# Peripherals.net
KiCad netlist of a schematic drawn in Altium Designer
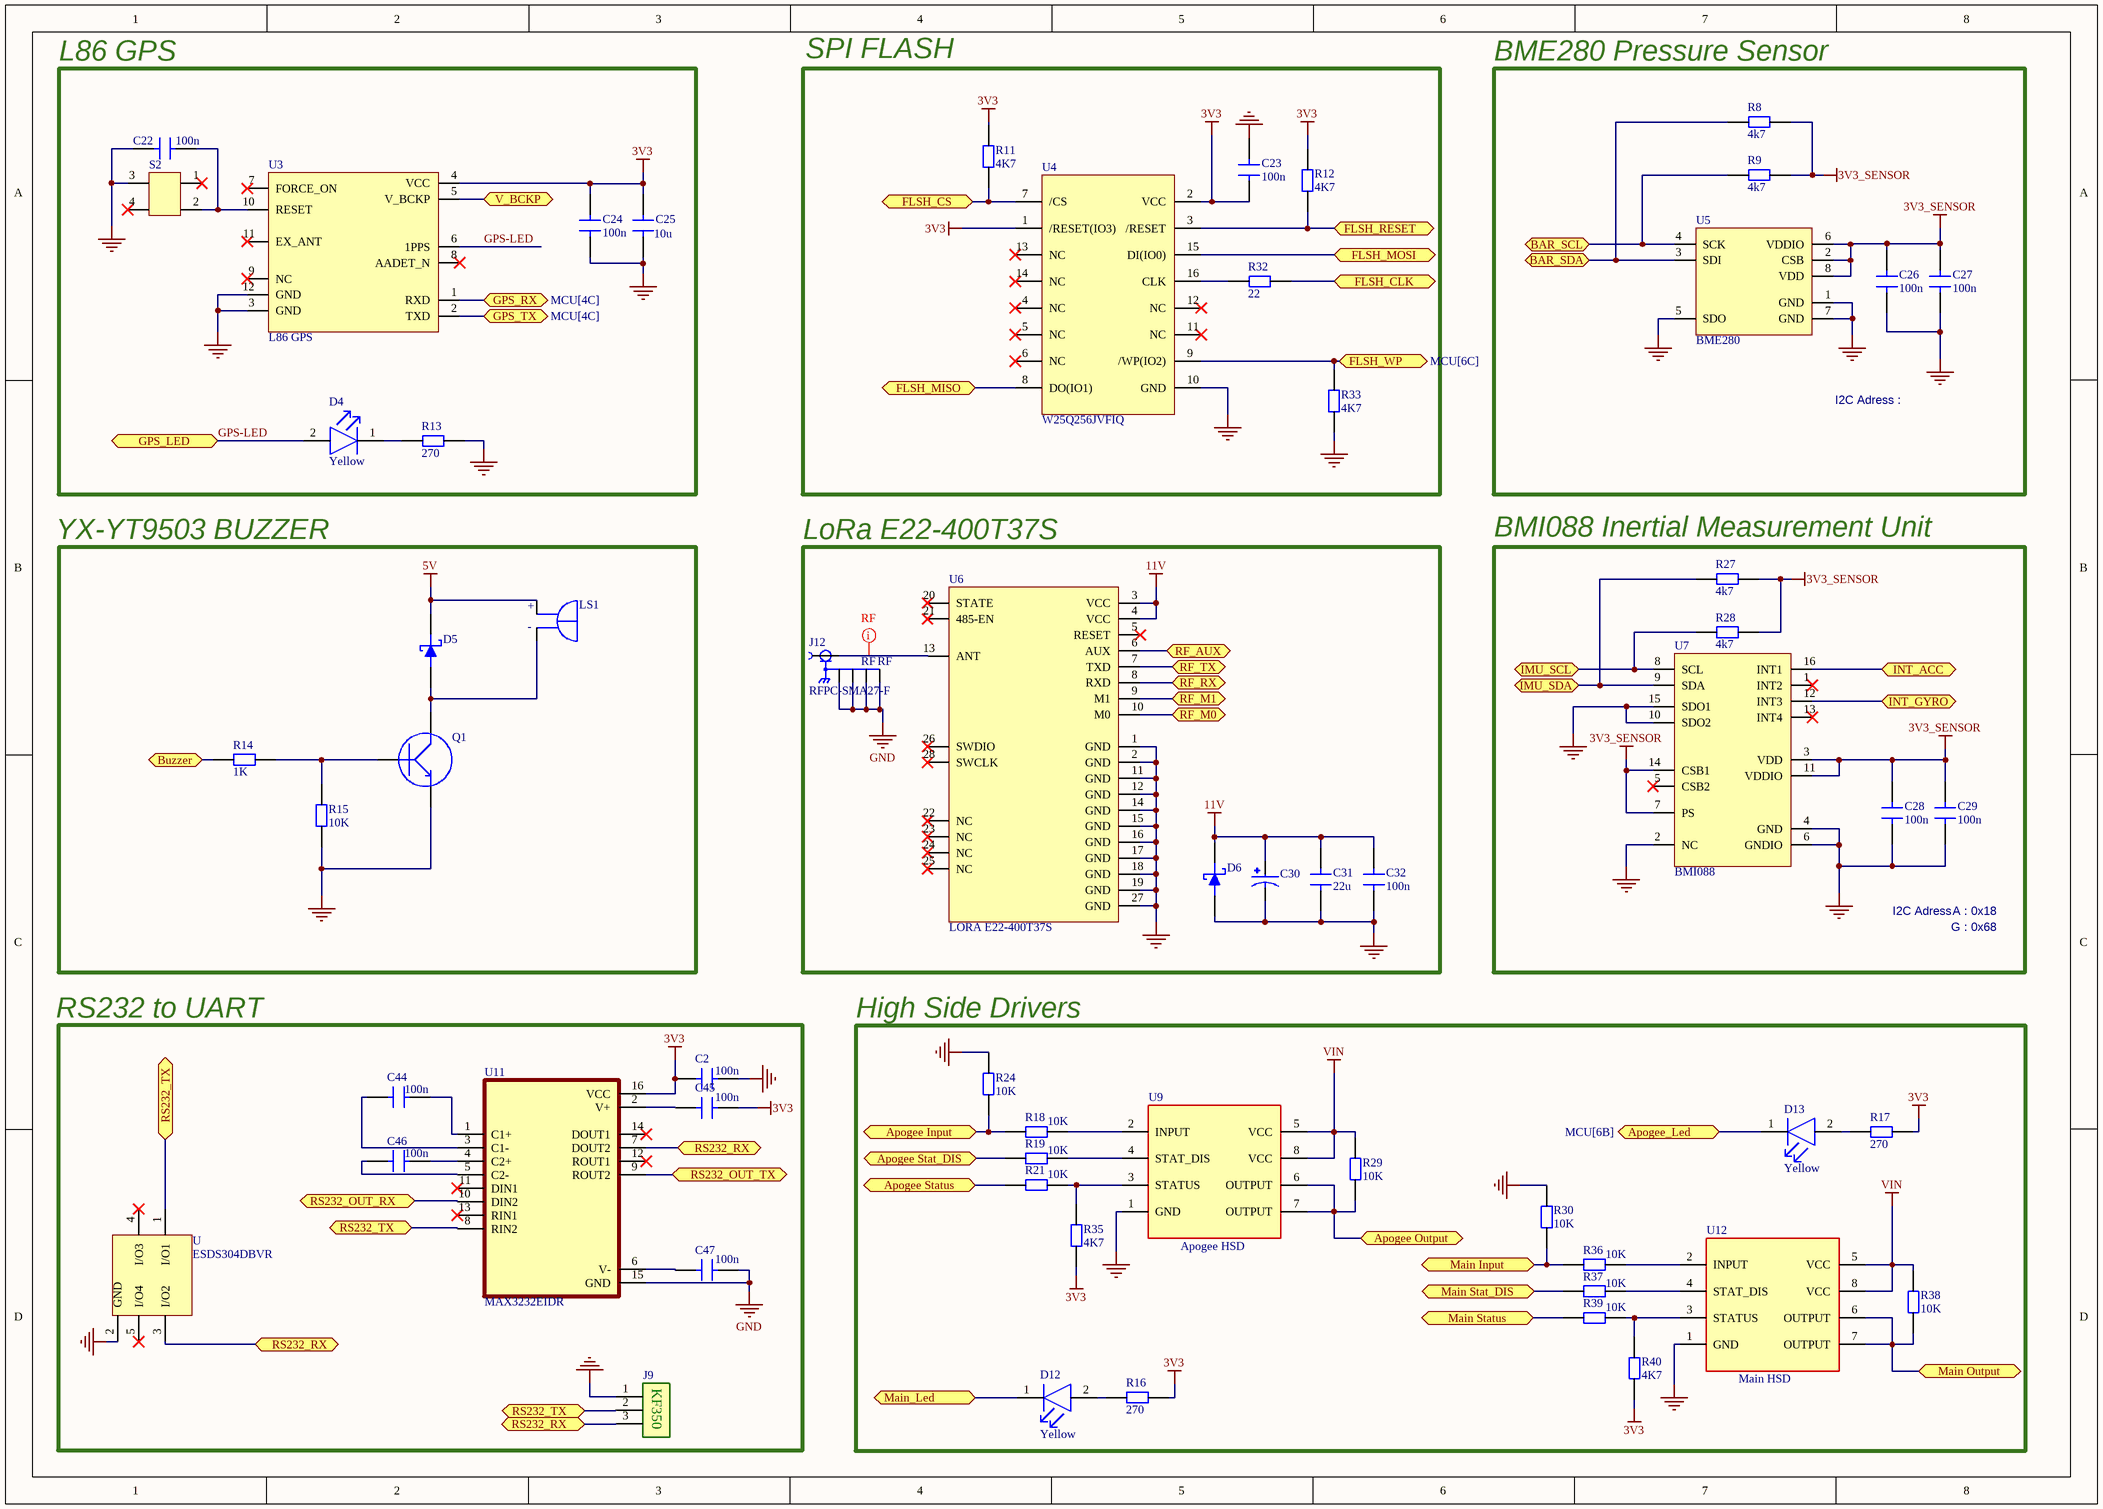
[diagram p0: Peripherals.SchDoc]

(export (version "E")
  (design (tool "Eeschema 10.0.6"))
  (components
    (comp (ref "C2")
      (value "100n")
      (footprint "CAP 0603")
      (description "Capacitor SMD 0603 25V")
      (libsource (lib "R_07_24-Schlib") (part "CAP 0603 25V"))
    )
    (comp (ref "C22")
      (value "100n")
      (footprint "CAP 0603")
      (description "Capacitor SMD 0603 50V")
      (libsource (lib "Schlib") (part "CAP 0603 50V"))
    )
    (comp (ref "C23")
      (value "100n")
      (footprint "CAP 0603")
      (description "Capacitor SMD 0603 50V")
      (libsource (lib "R_07_24-Schlib") (part "CAP 0603 50V"))
    )
    (comp (ref "C24")
      (value "100n")
      (footprint "CAP 0805")
      (description "Capacitor SMD 0805 50V")
      (libsource (lib "R_07_24-Schlib") (part "CAP 0805 50V"))
    )
    (comp (ref "C25")
      (value "10u")
      (footprint "CAP 0805")
      (description "Capacitor SMD 0805 25V")
      (libsource (lib "Schlib") (part "CAP 0805 25V"))
    )
    (comp (ref "C26")
      (value "100n")
      (footprint "CAP 0603")
      (description "Capacitor SMD 0603 50V")
      (libsource (lib "Schlib") (part "CAP 0603 50V"))
    )
    (comp (ref "C27")
      (value "100n")
      (footprint "CAP 0603")
      (description "Capacitor SMD 0603 50V")
      (libsource (lib "Schlib") (part "CAP 0603 50V"))
    )
    (comp (ref "C28")
      (value "100n")
      (footprint "CAP 0603")
      (description "Capacitor SMD 0603 50V")
      (libsource (lib "Schlib") (part "CAP 0603 50V"))
    )
    (comp (ref "C29")
      (value "100n")
      (footprint "CAP 0603")
      (description "Capacitor SMD 0603 50V")
      (libsource (lib "Schlib") (part "CAP 0603 50V"))
    )
    (comp (ref "C30")
      (value "EEEFK1E101XP")
      (footprint "CAP_EEEFK1E101XP")
      (fields (field (name "MF") "Panasonic"))
      (libsource (lib "2024_Temmuz") (part "100uF AL CAP"))
    )
    (comp (ref "C31")
      (value "22u")
      (footprint "CAP 1210")
      (description "Capacitor SMD 1210 25V")
      (libsource (lib "Schlib") (part "CAP 1210 25V"))
    )
    (comp (ref "C32")
      (value "100n")
      (footprint "CAP 0805")
      (description "Capacitor SMD 0805 50V")
      (libsource (lib "Schlib") (part "CAP 0805 50V"))
    )
    (comp (ref "C44")
      (value "100n")
      (footprint "CAP 0603")
      (description "Capacitor SMD 0603 25V")
      (libsource (lib "R_07_24-Schlib") (part "CAP 0603 25V"))
    )
    (comp (ref "C45")
      (value "100n")
      (footprint "CAP 0603")
      (description "Capacitor SMD 0603 25V")
      (libsource (lib "R_07_24-Schlib") (part "CAP 0603 25V"))
    )
    (comp (ref "C46")
      (value "100n")
      (footprint "CAP 0603")
      (description "Capacitor SMD 0603 25V")
      (libsource (lib "R_07_24-Schlib") (part "CAP 0603 25V"))
    )
    (comp (ref "C47")
      (value "100n")
      (footprint "CAP 0603")
      (description "Capacitor SMD 0603 25V")
      (libsource (lib "R_07_24-Schlib") (part "CAP 0603 25V"))
    )
    (comp (ref "D4")
      (value "Yellow")
      (footprint "FP-LTST-C170YKT-MFG")
      (description "LED YELLOW CLEAR SMD")
      (libsource (lib "Altium Content Vault") (part "590121a5bdfd2d28d8ee457b77c7368"))
    )
    (comp (ref "D5")
      (value "TMBAT49FILM")
      (footprint "TMBAT49FILM")
      (description "Rectifier Diode Small Signal Schottky Si 80V 0.5A 2-Pin MELF T/R")
      (fields (field (name "MANUFACTURER") "STMicroelectronics"))
      (libsource (lib "Schlib") (part "TMBAT49FILM"))
    )
    (comp (ref "D6")
      (value "SMBJ14CA")
      (footprint "SMBJ12CA-13-F")
      (description "TVS DIODE 14VWM 23.2VC DO214AA")
      (fields (field (name "MANUFACTURER") "Littelfuse") (field (name "VOLTAGE") "14V"))
      (libsource (lib "Schlib") (part "SMBJ14CA"))
    )
    (comp (ref "D12")
      (value "Yellow")
      (footprint "FP-LTST-C170YKT-MFG")
      (description "LED YELLOW CLEAR SMD")
      (libsource (lib "Altium Content Vault") (part "590121a5bdfd2d28d8ee457b77c7368"))
    )
    (comp (ref "D13")
      (value "Yellow")
      (footprint "FP-LTST-C170YKT-MFG")
      (description "LED YELLOW CLEAR SMD")
      (libsource (lib "Altium Content Vault") (part "590121a5bdfd2d28d8ee457b77c7368"))
    )
    (comp (ref "J9")
      (value "KF350-3P")
      (footprint "KF350-3P")
      (libsource (lib "2024_Temmuz") (part "KF350-3P"))
    )
    (comp (ref "J12")
      (value "RFPC-SMA27-F")
      (footprint "GRADCONN_RFPC-SMA27-F")
      (fields (field (name "MF") "{'manufacturer': u'GradConn'}"))
      (libsource (lib "2024_Temmuz") (part "RFPC-SMA27-F"))
    )
    (comp (ref "LS1")
      (value "KXG0912C")
      (footprint "XDCR_KXG0912C")
      (libsource (lib "2024_Temmuz") (part "KXG0912C"))
    )
    (comp (ref "Q1")
      (value "BC817-25W,115")
      (footprint "BC817-25")
      (description "BC817 Series 45 V 500 mA NPN General Purpose Transistor - SOT-23")
      (fields (field (name "MANUFACTURER") "Nexperia"))
      (libsource (lib "Schlib") (part "BC817-25W,115"))
    )
    (comp (ref "R8")
      (value "4k7")
      (footprint "RES 0603")
      (description "Resistor SMD 0603")
      (libsource (lib "Schlib") (part "RES 0603"))
    )
    (comp (ref "R9")
      (value "4k7")
      (footprint "RES 0603")
      (description "Resistor SMD 0603")
      (libsource (lib "Schlib") (part "RES 0603"))
    )
    (comp (ref "R11")
      (value "4K7")
      (footprint "RES 0805")
      (description "Resistor SMD 0805")
      (libsource (lib "R_07_24-Schlib") (part "RES 0805"))
    )
    (comp (ref "R12")
      (value "4K7")
      (footprint "RES 0805")
      (description "Resistor SMD 0805")
      (libsource (lib "R_07_24-Schlib") (part "RES 0805"))
    )
    (comp (ref "R13")
      (value "270")
      (footprint "RES 0805")
      (description "Resistor SMD 0805")
      (libsource (lib "R_07_24-Schlib") (part "RES 0805"))
    )
    (comp (ref "R14")
      (value "1K")
      (footprint "RES 0805")
      (description "Resistor SMD 0805")
      (libsource (lib "R_07_24-Schlib") (part "RES 0805"))
    )
    (comp (ref "R15")
      (value "10K")
      (footprint "RES 0805")
      (description "Resistor SMD 0805")
      (libsource (lib "R_07_24-Schlib") (part "RES 0805"))
    )
    (comp (ref "R16")
      (value "270")
      (footprint "RES 0805")
      (description "Resistor SMD 0805")
      (libsource (lib "R_07_24-Schlib") (part "RES 0805"))
    )
    (comp (ref "R17")
      (value "270")
      (footprint "RES 0805")
      (description "Resistor SMD 0805")
      (libsource (lib "R_07_24-Schlib") (part "RES 0805"))
    )
    (comp (ref "R18")
      (value "10K")
      (footprint "RES 0603")
      (description "Resistor SMD 0603")
      (libsource (lib "R_07_24-Schlib") (part "RES 0603"))
    )
    (comp (ref "R19")
      (value "10K")
      (footprint "RES 0603")
      (description "Resistor SMD 0603")
      (libsource (lib "R_07_24-Schlib") (part "RES 0603"))
    )
    (comp (ref "R21")
      (value "10K")
      (footprint "RES 0603")
      (description "Resistor SMD 0603")
      (libsource (lib "R_07_24-Schlib") (part "RES 0603"))
    )
    (comp (ref "R24")
      (value "10K")
      (footprint "RES 0603")
      (description "Resistor SMD 0603")
      (libsource (lib "R_07_24-Schlib") (part "RES 0603"))
    )
    (comp (ref "R27")
      (value "4k7")
      (footprint "RES 0603")
      (description "Resistor SMD 0603")
      (libsource (lib "Schlib") (part "RES 0603"))
    )
    (comp (ref "R28")
      (value "4k7")
      (footprint "RES 0603")
      (description "Resistor SMD 0603")
      (libsource (lib "Schlib") (part "RES 0603"))
    )
    (comp (ref "R29")
      (value "10K")
      (footprint "RES 0805")
      (description "Resistor SMD 0805")
      (libsource (lib "R_07_24-Schlib") (part "RES 0805"))
    )
    (comp (ref "R30")
      (value "10K")
      (footprint "RES 0603")
      (description "Resistor SMD 0603")
      (libsource (lib "R_07_24-Schlib") (part "RES 0603"))
    )
    (comp (ref "R32")
      (value "22")
      (footprint "RES 0603")
      (description "Resistor SMD 0603")
      (libsource (lib "R_07_24-Schlib") (part "RES 0603"))
    )
    (comp (ref "R33")
      (value "4K7")
      (footprint "RES 0603")
      (description "Resistor SMD 0603")
      (libsource (lib "") (part "RES 0603_1"))
    )
    (comp (ref "R35")
      (value "4K7")
      (footprint "RES 0603")
      (description "Resistor SMD 0603")
      (libsource (lib "R_07_24-Schlib") (part "RES 0603"))
    )
    (comp (ref "R36")
      (value "10K")
      (footprint "RES 0603")
      (description "Resistor SMD 0603")
      (libsource (lib "R_07_24-Schlib") (part "RES 0603"))
    )
    (comp (ref "R37")
      (value "10K")
      (footprint "RES 0603")
      (description "Resistor SMD 0603")
      (libsource (lib "R_07_24-Schlib") (part "RES 0603"))
    )
    (comp (ref "R38")
      (value "10K")
      (footprint "RES 0805")
      (description "Resistor SMD 0805")
      (libsource (lib "R_07_24-Schlib") (part "RES 0805"))
    )
    (comp (ref "R39")
      (value "10K")
      (footprint "RES 0603")
      (description "Resistor SMD 0603")
      (libsource (lib "R_07_24-Schlib") (part "RES 0603"))
    )
    (comp (ref "R40")
      (value "4K7")
      (footprint "RES 0603")
      (description "Resistor SMD 0603")
      (libsource (lib "R_07_24-Schlib") (part "RES 0603"))
    )
    (comp (ref "S2")
      (value "FSM4JSMATR")
      (footprint "FSM4JSMATR")
      (description "Switch Tactile OFF (ON) SPST Round Button Gull Wing 0.05A 24VDC 1.57N SMD T/R")
      (fields (field (name "MANUFACTURER") "TE Connectivity Alcoswitch"))
      (libsource (lib "Schlib") (part "FSM4JSMATR"))
    )
    (comp (ref "U")
      (value "ESDS304DBVR")
      (footprint "SOT95P280X145-5N")
      (description "2-channel, 3.6-V data-line surge and 30k-V ESD protection diode array 5-SOT-23 -40 to 125")
      (fields (field (name "MF") "Texas Instruments"))
      (libsource (lib "2024_Temmuz") (part "ESDS304DBVR"))
    )
    (comp (ref "U3") (value "L86 GPS") (footprint "L86") (libsource (lib "Schlib") (part "L86 GPS")))
    (comp (ref "U4")
      (value "W25Q256JVFIQ")
      (footprint "W25Q256JVFIQ")
      (libsource (lib "R_07_24-Schlib") (part "W25Q256JVFIQ"))
    )
    (comp (ref "U5")
      (value "BME280")
      (footprint "BME280")
      (description "SENSOR PRESSURE HUMIDITY TEMP")
      (fields (field (name "MANUFACTURER") "Bosch"))
      (libsource (lib "Schlib") (part "BME280"))
    )
    (comp (ref "U6")
      (value "LORA E22-400T37S")
      (footprint "LORA E22-400T37S")
      (description "E22-400T37S LoRa Module")
      (libsource (lib "Schlib") (part "LORA E22-400T37S"))
    )
    (comp (ref "U7")
      (value "BMI088")
      (footprint "BMI088")
      (description "BMI088 Series 3.6 V 6 Axis Digital Output Accelerometer Motion Sensor - LGA-16")
      (fields (field (name "MANUFACTURER") "Bosch Tools"))
      (libsource (lib "Schlib") (part "BMI088"))
    )
    (comp (ref "U9")
      (value "VN5E160STR-E")
      (footprint "VN5E160STR-E")
      (description "Power Switch/Driver 1:1 N-Channel 7A 8-SOIC \r\nHigh Side Driver")
      (fields (field (name "MF") "STMicroelectronics"))
      (libsource (lib "2024_Temmuz") (part "VN5E160STR-E"))
    )
    (comp (ref "U11")
      (value "MAX3232EIDR")
      (footprint "MAX3232EIDR")
      (description "3- to 5.5-V dual channel 250kbps RS-232 line driver/receiver with +/-15-kV IEC-ESD protection")
      (fields (field (name "MF") "Texas Instruments"))
      (libsource (lib "2024_Temmuz") (part "MAX3232EIDR"))
    )
    (comp (ref "U12")
      (value "VN5E160STR-E")
      (footprint "VN5E160STR-E")
      (description "Power Switch/Driver 1:1 N-Channel 7A 8-SOIC \r\nHigh Side Driver")
      (fields (field (name "MF") "STMicroelectronics"))
      (libsource (lib "2024_Temmuz") (part "VN5E160STR-E"))
    )
  )
  (nets
    (net (code "1") (name "/Apogee Input") (class "Default")
      (node (ref "R18") (pin "1") (pinfunction "1_1") (pintype "passive"))
      (node (ref "R24") (pin "1") (pinfunction "1_1") (pintype "passive"))
    )
    (net (code "2") (name "/Apogee Output") (class "Default")
      (node (ref "R29") (pin "1") (pinfunction "1_1") (pintype "passive"))
      (node (ref "U9") (pin "6") (pinfunction "OUTPUT_6") (pintype "passive"))
      (node (ref "U9") (pin "7") (pinfunction "OUTPUT_7") (pintype "passive"))
    )
    (net (code "3") (name "/Apogee Stat_DIS") (class "Default")
      (node (ref "R19") (pin "1") (pinfunction "1_1") (pintype "passive"))
    )
    (net (code "4") (name "/Apogee Status") (class "Default")
      (node (ref "R21") (pin "1") (pinfunction "1_1") (pintype "passive"))
    )
    (net (code "5") (name "/Apogee_Led") (class "Default")
      (node (ref "D13") (pin "1") (pinfunction "C_1") (pintype "passive"))
    )
    (net (code "6") (name "/BAR_SCL") (class "Default")
      (node (ref "R9") (pin "1") (pinfunction "1_1") (pintype "passive"))
      (node (ref "U5") (pin "4") (pinfunction "SCK_4") (pintype "passive"))
    )
    (net (code "7") (name "/BAR_SDA") (class "Default")
      (node (ref "R8") (pin "1") (pinfunction "1_1") (pintype "passive"))
      (node (ref "U5") (pin "3") (pinfunction "SDI_3") (pintype "passive"))
    )
    (net (code "8") (name "/Buzzer") (class "Default")
      (node (ref "R14") (pin "1") (pinfunction "1_1") (pintype "passive"))
    )
    (net (code "9") (name "/FLSH_CLK") (class "Default")
      (node (ref "R32") (pin "2") (pinfunction "2_2") (pintype "passive"))
    )
    (net (code "10") (name "/FLSH_CS") (class "Default")
      (node (ref "R11") (pin "1") (pinfunction "1_1") (pintype "passive"))
      (node (ref "U4") (pin "7") (pinfunction "/CS_7") (pintype "passive"))
    )
    (net (code "11") (name "/FLSH_MISO") (class "Default")
      (node (ref "U4") (pin "8") (pinfunction "DO(IO1)_8") (pintype "passive"))
    )
    (net (code "12") (name "/FLSH_MOSI") (class "Default")
      (node (ref "U4") (pin "15") (pinfunction "DI(IO0)_15") (pintype "passive"))
    )
    (net (code "13") (name "/FLSH_RESET") (class "Default")
      (node (ref "R12") (pin "1") (pinfunction "1_1") (pintype "passive"))
      (node (ref "U4") (pin "3") (pinfunction "/RESET_3") (pintype "passive"))
    )
    (net (code "14") (name "/FLSH_WP") (class "Default")
      (node (ref "R33") (pin "2") (pinfunction "2_2") (pintype "passive"))
      (node (ref "U4") (pin "9") (pinfunction "/WP(IO2)_9") (pintype "passive"))
    )
    (net (code "15") (name "/GPS-LED") (class "Default")
      (node (ref "D4") (pin "2") (pinfunction "A_2") (pintype "passive"))
      (node (ref "U3") (pin "6") (pinfunction "1PPS_6") (pintype "passive"))
    )
    (net (code "16") (name "/GPS_RX") (class "Default")
      (node (ref "U3") (pin "1") (pinfunction "RXD_1") (pintype "passive"))
    )
    (net (code "17") (name "/GPS_TX") (class "Default")
      (node (ref "U3") (pin "2") (pinfunction "TXD_2") (pintype "passive"))
    )
    (net (code "18") (name "/IMU_SCL") (class "Default")
      (node (ref "R28") (pin "1") (pinfunction "1_1") (pintype "passive"))
      (node (ref "U7") (pin "8") (pinfunction "SCL_8") (pintype "passive"))
    )
    (net (code "19") (name "/IMU_SDA") (class "Default")
      (node (ref "R27") (pin "1") (pinfunction "1_1") (pintype "passive"))
      (node (ref "U7") (pin "9") (pinfunction "SDA_9") (pintype "passive"))
    )
    (net (code "20") (name "/INT_ACC") (class "Default")
      (node (ref "U7") (pin "16") (pinfunction "INT1_16") (pintype "passive"))
    )
    (net (code "21") (name "/INT_GYRO") (class "Default")
      (node (ref "U7") (pin "12") (pinfunction "INT3_12") (pintype "passive"))
    )
    (net (code "23") (name "/Main Input") (class "Default")
      (node (ref "R30") (pin "1") (pinfunction "1_1") (pintype "passive"))
      (node (ref "R36") (pin "1") (pinfunction "1_1") (pintype "passive"))
    )
    (net (code "24") (name "/Main Output") (class "Default")
      (node (ref "R38") (pin "1") (pinfunction "1_1") (pintype "passive"))
      (node (ref "U12") (pin "6") (pinfunction "OUTPUT_6") (pintype "passive"))
      (node (ref "U12") (pin "7") (pinfunction "OUTPUT_7") (pintype "passive"))
    )
    (net (code "25") (name "/Main Stat_DIS") (class "Default")
      (node (ref "R37") (pin "1") (pinfunction "1_1") (pintype "passive"))
    )
    (net (code "26") (name "/Main Status") (class "Default")
      (node (ref "R39") (pin "1") (pinfunction "1_1") (pintype "passive"))
    )
    (net (code "27") (name "/Main_Led") (class "Default")
      (node (ref "D12") (pin "1") (pinfunction "C_1") (pintype "passive"))
    )
    (net (code "28") (name "/RF_AUX") (class "Default")
      (node (ref "U6") (pin "6") (pinfunction "AUX_6") (pintype "passive"))
    )
    (net (code "29") (name "/RF_M0") (class "Default")
      (node (ref "U6") (pin "10") (pinfunction "M0_10") (pintype "passive"))
    )
    (net (code "30") (name "/RF_M1") (class "Default")
      (node (ref "U6") (pin "9") (pinfunction "M1_9") (pintype "passive"))
    )
    (net (code "31") (name "/RF_RX") (class "Default")
      (node (ref "U6") (pin "8") (pinfunction "RXD_8") (pintype "passive"))
    )
    (net (code "32") (name "/RF_TX") (class "Default")
      (node (ref "U6") (pin "7") (pinfunction "TXD_7") (pintype "passive"))
    )
    (net (code "33") (name "/RS232_OUT_RX") (class "Default")
      (node (ref "U11") (pin "10") (pinfunction "DIN2_10") (pintype "passive"))
    )
    (net (code "34") (name "/RS232_OUT_TX") (class "Default")
      (node (ref "U11") (pin "9") (pinfunction "ROUT2_9") (pintype "passive"))
    )
    (net (code "35") (name "/RS232_RX") (class "Default")
      (node (ref "J9") (pin "3") (pinfunction "3_3") (pintype "passive"))
      (node (ref "U") (pin "3") (pinfunction "I/O2_3") (pintype "passive"))
      (node (ref "U11") (pin "7") (pinfunction "DOUT2_7") (pintype "passive"))
    )
    (net (code "36") (name "/RS232_TX") (class "Default")
      (node (ref "J9") (pin "2") (pinfunction "2_2") (pintype "passive"))
      (node (ref "U") (pin "1") (pinfunction "I/O1_1") (pintype "passive"))
      (node (ref "U11") (pin "8") (pinfunction "RIN2_8") (pintype "passive"))
    )
    (net (code "37") (name "/V_BCKP") (class "Default")
      (node (ref "U3") (pin "5") (pinfunction "V_BCKP_5") (pintype "passive"))
    )
    (net (code "38") (name "3V3") (class "Default")
      (node (ref "C2") (pin "1") (pinfunction "1_1") (pintype "passive"))
      (node (ref "C23") (pin "1") (pinfunction "1_1") (pintype "passive"))
      (node (ref "C24") (pin "2") (pinfunction "2_2") (pintype "passive"))
      (node (ref "C25") (pin "2") (pinfunction "2_2") (pintype "passive"))
      (node (ref "C45") (pin "2") (pinfunction "2_2") (pintype "passive"))
      (node (ref "R11") (pin "2") (pinfunction "2_2") (pintype "passive"))
      (node (ref "R12") (pin "2") (pinfunction "2_2") (pintype "passive"))
      (node (ref "R16") (pin "2") (pinfunction "2_2") (pintype "passive"))
      (node (ref "R17") (pin "2") (pinfunction "2_2") (pintype "passive"))
      (node (ref "R35") (pin "1") (pinfunction "1_1") (pintype "passive"))
      (node (ref "R40") (pin "1") (pinfunction "1_1") (pintype "passive"))
      (node (ref "U11") (pin "16") (pinfunction "VCC_16") (pintype "passive"))
      (node (ref "U3") (pin "4") (pinfunction "VCC_4") (pintype "passive"))
      (node (ref "U4") (pin "1") (pinfunction "/RESET(IO3)_1") (pintype "passive"))
      (node (ref "U4") (pin "2") (pinfunction "VCC_2") (pintype "passive"))
    )
    (net (code "39") (name "3V3_SENSOR") (class "Default")
      (node (ref "C26") (pin "2") (pinfunction "2_2") (pintype "passive"))
      (node (ref "C27") (pin "2") (pinfunction "2_2") (pintype "passive"))
      (node (ref "C28") (pin "2") (pinfunction "2_2") (pintype "passive"))
      (node (ref "C29") (pin "2") (pinfunction "2_2") (pintype "passive"))
      (node (ref "R27") (pin "2") (pinfunction "2_2") (pintype "passive"))
      (node (ref "R28") (pin "2") (pinfunction "2_2") (pintype "passive"))
      (node (ref "R8") (pin "2") (pinfunction "2_2") (pintype "passive"))
      (node (ref "R9") (pin "2") (pinfunction "2_2") (pintype "passive"))
      (node (ref "U5") (pin "2") (pinfunction "CSB_2") (pintype "passive"))
      (node (ref "U5") (pin "6") (pinfunction "VDDIO_6") (pintype "passive"))
      (node (ref "U5") (pin "8") (pinfunction "VDD_8") (pintype "passive"))
      (node (ref "U7") (pin "11") (pinfunction "VDDIO_11") (pintype "passive"))
      (node (ref "U7") (pin "14") (pinfunction "CSB1_14") (pintype "passive"))
      (node (ref "U7") (pin "3") (pinfunction "VDD_3") (pintype "passive"))
      (node (ref "U7") (pin "7") (pinfunction "PS_7") (pintype "passive"))
    )
    (net (code "40") (name "5V") (class "Default")
      (node (ref "D5") (pin "1") (pintype "passive"))
      (node (ref "LS1") (pin "P") (pinfunction "POS_P") (pintype "passive"))
    )
    (net (code "41") (name "11V") (class "Default")
      (node (ref "C30") (pin "1") (pinfunction "1_1") (pintype "passive"))
      (node (ref "C31") (pin "2") (pinfunction "2_2") (pintype "passive"))
      (node (ref "C32") (pin "2") (pinfunction "2_2") (pintype "passive"))
      (node (ref "D6") (pin "2") (pintype "passive"))
      (node (ref "U6") (pin "3") (pinfunction "VCC_3") (pintype "passive"))
      (node (ref "U6") (pin "4") (pinfunction "VCC_4") (pintype "passive"))
    )
    (net (code "42") (name "GND") (class "Default")
      (node (ref "C2") (pin "2") (pinfunction "2_2") (pintype "passive"))
      (node (ref "C22") (pin "1") (pinfunction "1_1") (pintype "passive"))
      (node (ref "C23") (pin "2") (pinfunction "2_2") (pintype "passive"))
      (node (ref "C24") (pin "1") (pinfunction "1_1") (pintype "passive"))
      (node (ref "C25") (pin "1") (pinfunction "1_1") (pintype "passive"))
      (node (ref "C26") (pin "1") (pinfunction "1_1") (pintype "passive"))
      (node (ref "C27") (pin "1") (pinfunction "1_1") (pintype "passive"))
      (node (ref "C28") (pin "1") (pinfunction "1_1") (pintype "passive"))
      (node (ref "C29") (pin "1") (pinfunction "1_1") (pintype "passive"))
      (node (ref "C30") (pin "2") (pinfunction "2_2") (pintype "passive"))
      (node (ref "C31") (pin "1") (pinfunction "1_1") (pintype "passive"))
      (node (ref "C32") (pin "1") (pinfunction "1_1") (pintype "passive"))
      (node (ref "C47") (pin "2") (pinfunction "2_2") (pintype "passive"))
      (node (ref "D6") (pin "1") (pintype "passive"))
      (node (ref "J12") (pin "G1") (pinfunction "G1_G1") (pintype "power_in"))
      (node (ref "J12") (pin "G2") (pinfunction "G2_G2") (pintype "power_in"))
      (node (ref "J12") (pin "G3") (pinfunction "G3_G3") (pintype "power_in"))
      (node (ref "J12") (pin "G4") (pinfunction "G4_G4") (pintype "power_in"))
      (node (ref "J9") (pin "1") (pinfunction "1_1") (pintype "passive"))
      (node (ref "Q1") (pin "2") (pinfunction "E_2") (pintype "passive"))
      (node (ref "R13") (pin "2") (pinfunction "2_2") (pintype "passive"))
      (node (ref "R15") (pin "1") (pinfunction "1_1") (pintype "passive"))
      (node (ref "R24") (pin "2") (pinfunction "2_2") (pintype "passive"))
      (node (ref "R30") (pin "2") (pinfunction "2_2") (pintype "passive"))
      (node (ref "R33") (pin "1") (pinfunction "1_1") (pintype "passive"))
      (node (ref "S2") (pin "3") (pinfunction "3_3") (pintype "passive"))
      (node (ref "U") (pin "2") (pinfunction "GND_2") (pintype "passive"))
      (node (ref "U11") (pin "15") (pinfunction "GND_15") (pintype "passive"))
      (node (ref "U12") (pin "1") (pinfunction "GND_1") (pintype "passive"))
      (node (ref "U3") (pin "12") (pinfunction "GND_12") (pintype "passive"))
      (node (ref "U3") (pin "3") (pinfunction "GND_3") (pintype "passive"))
      (node (ref "U4") (pin "10") (pinfunction "GND_10") (pintype "passive"))
      (node (ref "U5") (pin "1") (pinfunction "GND_1") (pintype "passive"))
      (node (ref "U5") (pin "5") (pinfunction "SDO_5") (pintype "passive"))
      (node (ref "U5") (pin "7") (pinfunction "GND_7") (pintype "passive"))
      (node (ref "U6") (pin "1") (pinfunction "GND_1") (pintype "passive"))
      (node (ref "U6") (pin "11") (pinfunction "GND_11") (pintype "passive"))
      (node (ref "U6") (pin "12") (pinfunction "GND_12") (pintype "passive"))
      (node (ref "U6") (pin "14") (pinfunction "GND_14") (pintype "passive"))
      (node (ref "U6") (pin "15") (pinfunction "GND_15") (pintype "passive"))
      (node (ref "U6") (pin "16") (pinfunction "GND_16") (pintype "passive"))
      (node (ref "U6") (pin "17") (pinfunction "GND_17") (pintype "passive"))
      (node (ref "U6") (pin "18") (pinfunction "GND_18") (pintype "passive"))
      (node (ref "U6") (pin "19") (pinfunction "GND_19") (pintype "passive"))
      (node (ref "U6") (pin "2") (pinfunction "GND_2") (pintype "passive"))
      (node (ref "U6") (pin "27") (pinfunction "GND_27") (pintype "passive"))
      (node (ref "U7") (pin "10") (pinfunction "SDO2_10") (pintype "passive"))
      (node (ref "U7") (pin "15") (pinfunction "SDO1_15") (pintype "passive"))
      (node (ref "U7") (pin "2") (pinfunction "NC_2") (pintype "passive"))
      (node (ref "U7") (pin "4") (pinfunction "GND_4") (pintype "passive"))
      (node (ref "U7") (pin "6") (pinfunction "GNDIO_6") (pintype "passive"))
      (node (ref "U9") (pin "1") (pinfunction "GND_1") (pintype "passive"))
    )
    (net (code "43") (name "Net-(D4-C)") (class "Default")
      (node (ref "D4") (pin "1") (pinfunction "C_1") (pintype "passive"))
      (node (ref "R13") (pin "1") (pinfunction "1_1") (pintype "passive"))
    )
    (net (code "44") (name "Net-(D12-A)") (class "Default")
      (node (ref "D12") (pin "2") (pinfunction "A_2") (pintype "passive"))
      (node (ref "R16") (pin "1") (pinfunction "1_1") (pintype "passive"))
    )
    (net (code "45") (name "Net-(D13-A)") (class "Default")
      (node (ref "D13") (pin "2") (pinfunction "A_2") (pintype "passive"))
      (node (ref "R17") (pin "1") (pinfunction "1_1") (pintype "passive"))
    )
    (net (code "46") (name "Net-(LS1-NEG)") (class "Default")
      (node (ref "D5") (pin "2") (pintype "passive"))
      (node (ref "LS1") (pin "N") (pinfunction "NEG_N") (pintype "passive"))
      (node (ref "Q1") (pin "3") (pinfunction "C_3") (pintype "passive"))
    )
    (net (code "47") (name "Net-(Q1-B)") (class "Default")
      (node (ref "Q1") (pin "1") (pinfunction "B_1") (pintype "passive"))
      (node (ref "R14") (pin "2") (pinfunction "2_2") (pintype "passive"))
      (node (ref "R15") (pin "2") (pinfunction "2_2") (pintype "passive"))
    )
    (net (code "48") (name "Net-(U3-RESET)") (class "Default")
      (node (ref "C22") (pin "2") (pinfunction "2_2") (pintype "passive"))
      (node (ref "S2") (pin "2") (pinfunction "2_2") (pintype "passive"))
      (node (ref "U3") (pin "10") (pinfunction "RESET_10") (pintype "passive"))
    )
    (net (code "49") (name "Net-(U4-CLK)") (class "Default")
      (node (ref "R32") (pin "1") (pinfunction "1_1") (pintype "passive"))
      (node (ref "U4") (pin "16") (pinfunction "CLK_16") (pintype "passive"))
    )
    (net (code "50") (name "Net-(U6-ANT)") (class "Default")
      (node (ref "J12") (pin "1") (pinfunction "1_1") (pintype "passive"))
      (node (ref "U6") (pin "13") (pinfunction "ANT_13") (pintype "passive"))
    )
    (net (code "51") (name "Net-(U9-INPUT)") (class "Default")
      (node (ref "R18") (pin "2") (pinfunction "2_2") (pintype "passive"))
      (node (ref "U9") (pin "2") (pinfunction "INPUT_2") (pintype "passive"))
    )
    (net (code "52") (name "Net-(U9-STATUS)") (class "Default")
      (node (ref "R21") (pin "2") (pinfunction "2_2") (pintype "passive"))
      (node (ref "R35") (pin "2") (pinfunction "2_2") (pintype "passive"))
      (node (ref "U9") (pin "3") (pinfunction "STATUS_3") (pintype "passive"))
    )
    (net (code "53") (name "Net-(U9-STAT_DIS)") (class "Default")
      (node (ref "R19") (pin "2") (pinfunction "2_2") (pintype "passive"))
      (node (ref "U9") (pin "4") (pinfunction "STAT_DIS_4") (pintype "passive"))
    )
    (net (code "54") (name "Net-(U11-C1+)") (class "Default")
      (node (ref "C44") (pin "2") (pinfunction "2_2") (pintype "passive"))
      (node (ref "U11") (pin "1") (pinfunction "C1+_1") (pintype "passive"))
    )
    (net (code "55") (name "Net-(U11-C1-)") (class "Default")
      (node (ref "C44") (pin "1") (pinfunction "1_1") (pintype "passive"))
      (node (ref "U11") (pin "3") (pinfunction "C1-_3") (pintype "passive"))
    )
    (net (code "56") (name "Net-(U11-C2+)") (class "Default")
      (node (ref "C46") (pin "2") (pinfunction "2_2") (pintype "passive"))
      (node (ref "U11") (pin "4") (pinfunction "C2+_4") (pintype "passive"))
    )
    (net (code "57") (name "Net-(U11-C2-)") (class "Default")
      (node (ref "C46") (pin "1") (pinfunction "1_1") (pintype "passive"))
      (node (ref "U11") (pin "5") (pinfunction "C2-_5") (pintype "passive"))
    )
    (net (code "58") (name "Net-(U11-V+)") (class "Default")
      (node (ref "C45") (pin "1") (pinfunction "1_1") (pintype "passive"))
      (node (ref "U11") (pin "2") (pinfunction "V+_2") (pintype "passive"))
    )
    (net (code "59") (name "Net-(U11-V-)") (class "Default")
      (node (ref "C47") (pin "1") (pinfunction "1_1") (pintype "passive"))
      (node (ref "U11") (pin "6") (pinfunction "V-_6") (pintype "passive"))
    )
    (net (code "60") (name "Net-(U12-INPUT)") (class "Default")
      (node (ref "R36") (pin "2") (pinfunction "2_2") (pintype "passive"))
      (node (ref "U12") (pin "2") (pinfunction "INPUT_2") (pintype "passive"))
    )
    (net (code "61") (name "Net-(U12-STATUS)") (class "Default")
      (node (ref "R39") (pin "2") (pinfunction "2_2") (pintype "passive"))
      (node (ref "R40") (pin "2") (pinfunction "2_2") (pintype "passive"))
      (node (ref "U12") (pin "3") (pinfunction "STATUS_3") (pintype "passive"))
    )
    (net (code "62") (name "Net-(U12-STAT_DIS)") (class "Default")
      (node (ref "R37") (pin "2") (pinfunction "2_2") (pintype "passive"))
      (node (ref "U12") (pin "4") (pinfunction "STAT_DIS_4") (pintype "passive"))
    )
    (net (code "63") (name "VIN") (class "Default")
      (node (ref "R29") (pin "2") (pinfunction "2_2") (pintype "passive"))
      (node (ref "R38") (pin "2") (pinfunction "2_2") (pintype "passive"))
      (node (ref "U12") (pin "5") (pinfunction "VCC_5") (pintype "passive"))
      (node (ref "U12") (pin "8") (pinfunction "VCC_8") (pintype "passive"))
      (node (ref "U9") (pin "5") (pinfunction "VCC_5") (pintype "passive"))
      (node (ref "U9") (pin "8") (pinfunction "VCC_8") (pintype "passive"))
    )
    (net (code "64") (name "unconnected-(S2-Pad1)") (class "Default")
      (node (ref "S2") (pin "1") (pinfunction "1_1") (pintype "passive+no_connect"))
    )
    (net (code "65") (name "unconnected-(S2-Pad4)") (class "Default")
      (node (ref "S2") (pin "4") (pinfunction "4_4") (pintype "passive+no_connect"))
    )
    (net (code "66") (name "unconnected-(U-I{slash}O3-Pad4)") (class "Default")
      (node (ref "U") (pin "4") (pinfunction "I/O3_4") (pintype "passive+no_connect"))
    )
    (net (code "67") (name "unconnected-(U-I{slash}O4-Pad5)") (class "Default")
      (node (ref "U") (pin "5") (pinfunction "I/O4_5") (pintype "passive+no_connect"))
    )
    (net (code "68") (name "unconnected-(U3-AADET_N-Pad8)") (class "Default")
      (node (ref "U3") (pin "8") (pinfunction "AADET_N_8") (pintype "passive+no_connect"))
    )
    (net (code "69") (name "unconnected-(U3-EX_ANT-Pad11)") (class "Default")
      (node (ref "U3") (pin "11") (pinfunction "EX_ANT_11") (pintype "passive+no_connect"))
    )
    (net (code "70") (name "unconnected-(U3-FORCE_ON-Pad7)") (class "Default")
      (node (ref "U3") (pin "7") (pinfunction "FORCE_ON_7") (pintype "passive+no_connect"))
    )
    (net (code "71") (name "unconnected-(U3-NC-Pad9)") (class "Default")
      (node (ref "U3") (pin "9") (pinfunction "NC_9") (pintype "passive+no_connect"))
    )
    (net (code "72") (name "unconnected-(U4-NC-Pad4)") (class "Default")
      (node (ref "U4") (pin "4") (pinfunction "NC_4") (pintype "passive+no_connect"))
    )
    (net (code "73") (name "unconnected-(U4-NC-Pad5)") (class "Default")
      (node (ref "U4") (pin "5") (pinfunction "NC_5") (pintype "passive+no_connect"))
    )
    (net (code "74") (name "unconnected-(U4-NC-Pad6)") (class "Default")
      (node (ref "U4") (pin "6") (pinfunction "NC_6") (pintype "passive+no_connect"))
    )
    (net (code "75") (name "unconnected-(U4-NC-Pad11)") (class "Default")
      (node (ref "U4") (pin "11") (pinfunction "NC_11") (pintype "passive+no_connect"))
    )
    (net (code "76") (name "unconnected-(U4-NC-Pad12)") (class "Default")
      (node (ref "U4") (pin "12") (pinfunction "NC_12") (pintype "passive+no_connect"))
    )
    (net (code "77") (name "unconnected-(U4-NC-Pad13)") (class "Default")
      (node (ref "U4") (pin "13") (pinfunction "NC_13") (pintype "passive+no_connect"))
    )
    (net (code "78") (name "unconnected-(U4-NC-Pad14)") (class "Default")
      (node (ref "U4") (pin "14") (pinfunction "NC_14") (pintype "passive+no_connect"))
    )
    (net (code "79") (name "unconnected-(U6-485-EN-Pad21)") (class "Default")
      (node (ref "U6") (pin "21") (pinfunction "485-EN_21") (pintype "passive+no_connect"))
    )
    (net (code "80") (name "unconnected-(U6-NC-Pad22)") (class "Default")
      (node (ref "U6") (pin "22") (pinfunction "NC_22") (pintype "passive+no_connect"))
    )
    (net (code "81") (name "unconnected-(U6-NC-Pad23)") (class "Default")
      (node (ref "U6") (pin "23") (pinfunction "NC_23") (pintype "passive+no_connect"))
    )
    (net (code "82") (name "unconnected-(U6-NC-Pad24)") (class "Default")
      (node (ref "U6") (pin "24") (pinfunction "NC_24") (pintype "passive+no_connect"))
    )
    (net (code "83") (name "unconnected-(U6-NC-Pad25)") (class "Default")
      (node (ref "U6") (pin "25") (pinfunction "NC_25") (pintype "passive+no_connect"))
    )
    (net (code "84") (name "unconnected-(U6-RESET-Pad5)") (class "Default")
      (node (ref "U6") (pin "5") (pinfunction "RESET_5") (pintype "passive+no_connect"))
    )
    (net (code "85") (name "unconnected-(U6-STATE-Pad20)") (class "Default")
      (node (ref "U6") (pin "20") (pinfunction "STATE_20") (pintype "passive+no_connect"))
    )
    (net (code "86") (name "unconnected-(U6-SWCLK-Pad28)") (class "Default")
      (node (ref "U6") (pin "28") (pinfunction "SWCLK_28") (pintype "passive+no_connect"))
    )
    (net (code "87") (name "unconnected-(U6-SWDIO-Pad26)") (class "Default")
      (node (ref "U6") (pin "26") (pinfunction "SWDIO_26") (pintype "passive+no_connect"))
    )
    (net (code "88") (name "unconnected-(U7-CSB2-Pad5)") (class "Default")
      (node (ref "U7") (pin "5") (pinfunction "CSB2_5") (pintype "passive+no_connect"))
    )
    (net (code "89") (name "unconnected-(U7-INT2-Pad1)") (class "Default")
      (node (ref "U7") (pin "1") (pinfunction "INT2_1") (pintype "passive+no_connect"))
    )
    (net (code "90") (name "unconnected-(U7-INT4-Pad13)") (class "Default")
      (node (ref "U7") (pin "13") (pinfunction "INT4_13") (pintype "passive+no_connect"))
    )
    (net (code "91") (name "unconnected-(U11-DIN1-Pad11)") (class "Default")
      (node (ref "U11") (pin "11") (pinfunction "DIN1_11") (pintype "passive+no_connect"))
    )
    (net (code "92") (name "unconnected-(U11-DOUT1-Pad14)") (class "Default")
      (node (ref "U11") (pin "14") (pinfunction "DOUT1_14") (pintype "passive+no_connect"))
    )
    (net (code "93") (name "unconnected-(U11-RIN1-Pad13)") (class "Default")
      (node (ref "U11") (pin "13") (pinfunction "RIN1_13") (pintype "passive+no_connect"))
    )
    (net (code "94") (name "unconnected-(U11-ROUT1-Pad12)") (class "Default")
      (node (ref "U11") (pin "12") (pinfunction "ROUT1_12") (pintype "passive+no_connect"))
    )
  )
)
